# HighSideDriver.net
KiCad netlist of a schematic drawn in Altium Designer
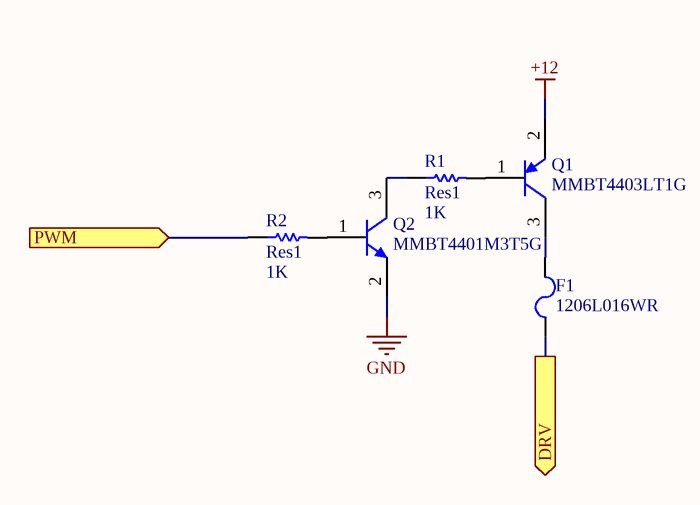
[diagram p0: HighSideDriver.SchDoc]

(export (version "E")
  (design (tool "Eeschema 10.0.6"))
  (components
    (comp (ref "F1")
      (value "1206L016WR")
      (footprint "LFUS-1206L016WR_V")
      (description "Resettable Fuse, 30 V, 100 A, 4.5 Ohm, -40 to 85 degC, 1206 (3216 Metric), RoHS, Tape and Reel")
      (fields (field (name "MANUFACTURER") "Littelfuse"))
      (libsource (lib "Altium Content Vault") (part "FUSE-2"))
    )
    (comp (ref "Q1")
      (value "MMBT4403LT1G")
      (footprint "ONSC-SOT-23-3-318-08_V")
      (description "Switching Transistor, PNP Silicon, 3-Pin SOT-23, Pb-Free, Tape and Reel")
      (fields (field (name "MANUFACTURER") "On Semiconductor"))
      (libsource (lib "Altium Content Vault") (part "CMP-1048-00539-1"))
    )
    (comp (ref "Q2")
      (value "MMBT4401M3T5G")
      (footprint "ONSC-SOT-23-3-318-08_V")
      (description "Switching Transistor, NPN Silicon, 3-Pin SOT-23, Pb-Free, Tape and Reel")
      (fields (field (name "MANUFACTURER") "On Semiconductor") (field (name "PARTNUMBER") "MMBT4401LT3G"))
      (libsource (lib "Altium Content Vault") (part "CMP-1048-00548-1"))
    )
    (comp (ref "R1")
      (value "Res1")
      (footprint "J1-0603")
      (description "Resistor")
      (fields (field (name "ALTIUM_VALUE") "1K") (field (name "PUBLISHER") "Altium Limited"))
      (libsource (lib "Miscellaneous Devices") (part "Res1"))
    )
    (comp (ref "R2")
      (value "Res1")
      (footprint "J1-0603")
      (description "Resistor")
      (fields (field (name "ALTIUM_VALUE") "1K") (field (name "PUBLISHER") "Altium Limited"))
      (libsource (lib "Miscellaneous Devices") (part "Res1"))
    )
  )
  (nets
    (net (code "1") (name "+12") (class "Default")
      (node (ref "Q1") (pin "2") (pinfunction "E_2") (pintype "passive"))
    )
    (net (code "2") (name "/DRV") (class "Default")
      (node (ref "F1") (pin "1") (pinfunction "1_1") (pintype "passive"))
    )
    (net (code "3") (name "/PWM") (class "Default")
      (node (ref "R2") (pin "1") (pinfunction "1_1") (pintype "passive"))
    )
    (net (code "4") (name "GND") (class "Default")
      (node (ref "Q2") (pin "2") (pinfunction "E_2") (pintype "passive"))
    )
    (net (code "5") (name "Net-(Q1-B)") (class "Default")
      (node (ref "Q1") (pin "1") (pinfunction "B_1") (pintype "passive"))
      (node (ref "R1") (pin "2") (pinfunction "2_2") (pintype "passive"))
    )
    (net (code "6") (name "Net-(Q1-C)") (class "Default")
      (node (ref "F1") (pin "2") (pinfunction "2_2") (pintype "passive"))
      (node (ref "Q1") (pin "3") (pinfunction "C_3") (pintype "passive"))
    )
    (net (code "7") (name "Net-(Q2-B)") (class "Default")
      (node (ref "Q2") (pin "1") (pinfunction "B_1") (pintype "passive"))
      (node (ref "R2") (pin "2") (pinfunction "2_2") (pintype "passive"))
    )
    (net (code "8") (name "Net-(Q2-C)") (class "Default")
      (node (ref "Q2") (pin "3") (pinfunction "C_3") (pintype "passive"))
      (node (ref "R1") (pin "1") (pinfunction "1_1") (pintype "passive"))
    )
  )
)
